# Groupe_2_final_PCB.net
KiCad netlist of a schematic drawn in EAGLE
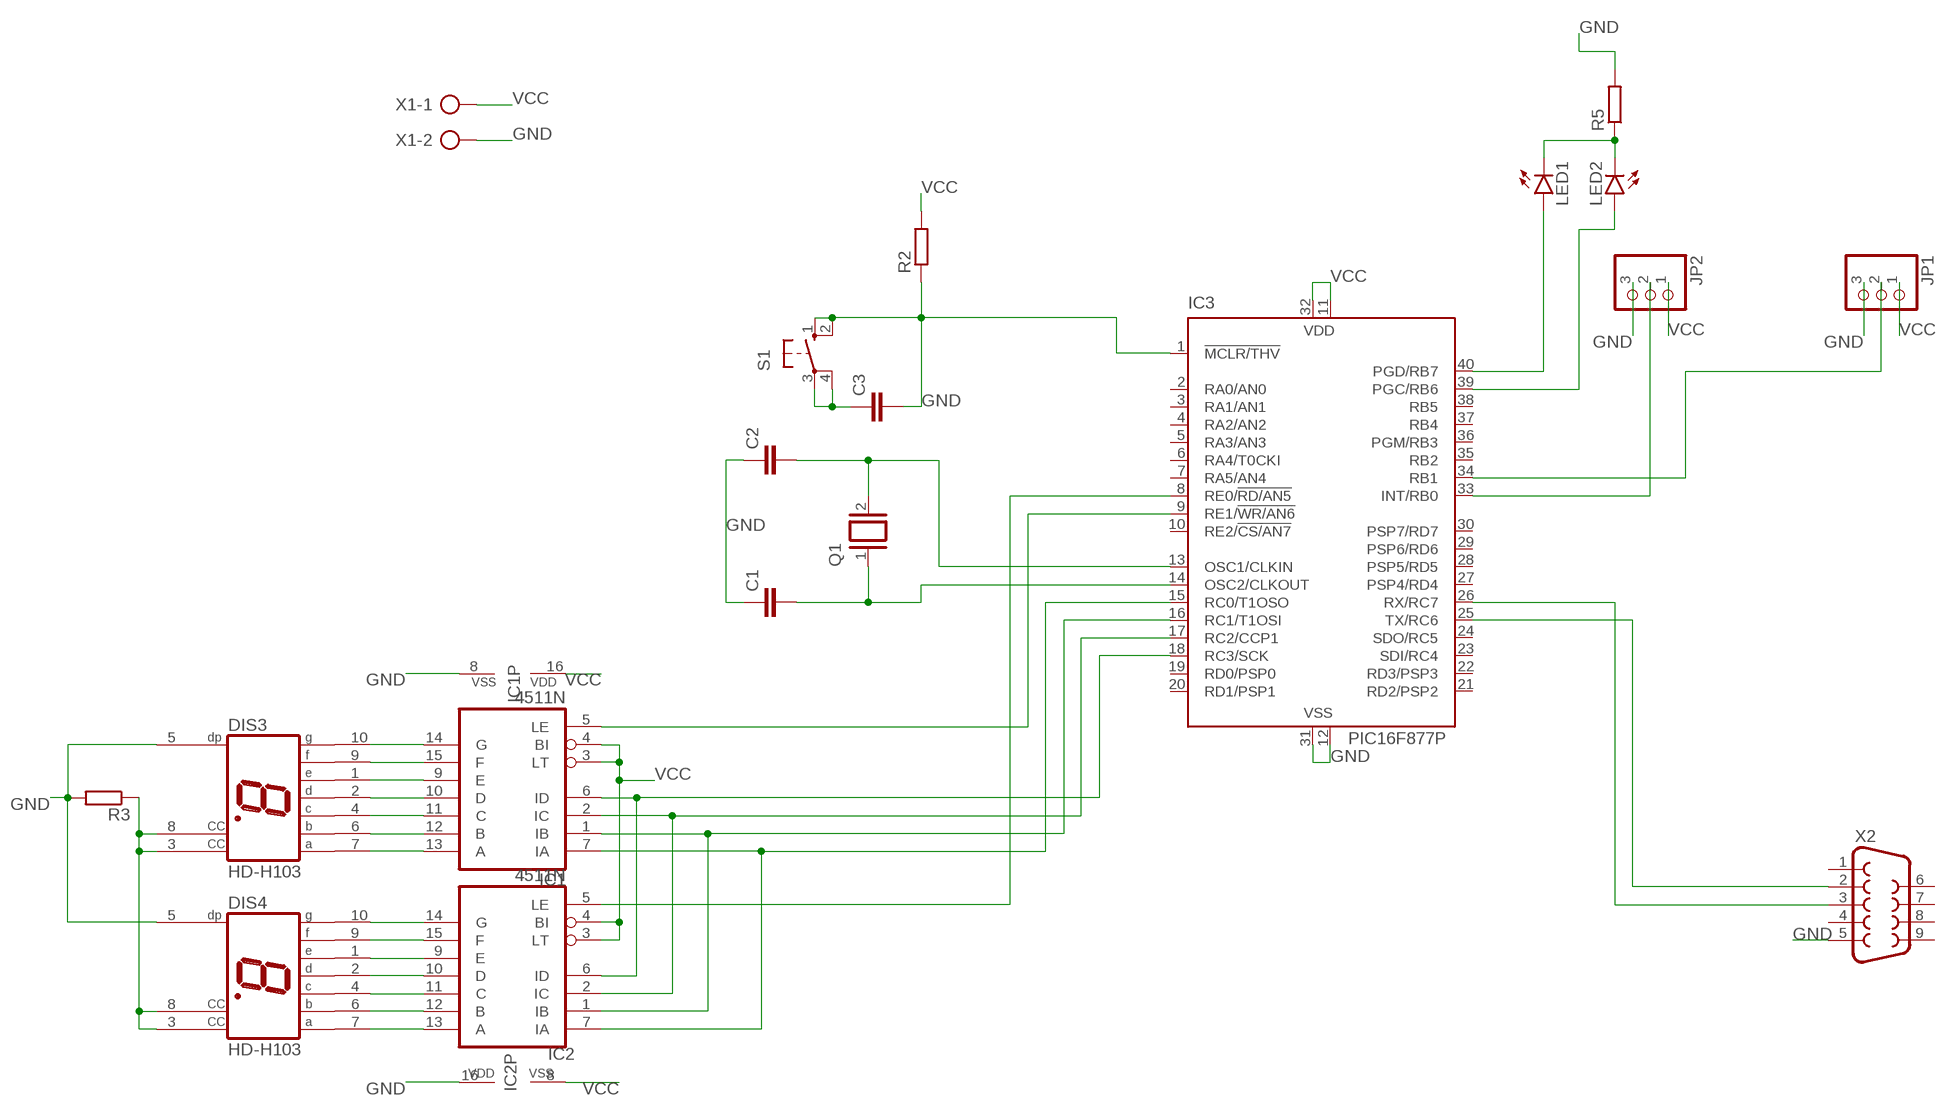
[diagram p0: schematic, sheet 1]

(export (version "E")
  (design (tool "Eeschema 10.0.6"))
  (components
    (comp (ref "C1")
      (value "C-EU025-025X050")
      (footprint "eagle-import:C025-025X050")
      (libsource (lib "eagle-import") (part "C-EU025-025X050"))
    )
    (comp (ref "C2")
      (value "C-EU025-025X050")
      (footprint "eagle-import:C025-025X050")
      (libsource (lib "eagle-import") (part "C-EU025-025X050"))
    )
    (comp (ref "C3")
      (value "C-EU025-025X050")
      (footprint "eagle-import:C025-025X050")
      (libsource (lib "eagle-import") (part "C-EU025-025X050"))
    )
    (comp (ref "DIS3")
      (value "HD-H103")
      (footprint "eagle-import:HDSP-M")
      (libsource (lib "eagle-import") (part "HD-H103"))
    )
    (comp (ref "DIS4")
      (value "HD-H103")
      (footprint "eagle-import:HDSP-M")
      (libsource (lib "eagle-import") (part "HD-H103"))
    )
    (comp (ref "IC1")
      (value "4511N")
      (footprint "eagle-import:DIL16")
      (libsource (lib "eagle-import") (part "4511N"))
    )
    (comp (ref "IC2")
      (value "4511N")
      (footprint "eagle-import:DIL16")
      (libsource (lib "eagle-import") (part "4511N"))
    )
    (comp (ref "IC3")
      (value "PIC16F877P")
      (footprint "eagle-import:DIL40")
      (fields (field (name "MF") "MICROCHIP") (field (name "MPN") "PIC16F877-04/P"))
      (libsource (lib "eagle-import") (part "PIC16F87P7"))
    )
    (comp (ref "JP1")
      (value "PINHD-1X3")
      (footprint "eagle-import:1X03")
      (libsource (lib "eagle-import") (part "PINHD-1X3"))
    )
    (comp (ref "JP2")
      (value "PINHD-1X3")
      (footprint "eagle-import:1X03")
      (libsource (lib "eagle-import") (part "PINHD-1X3"))
    )
    (comp (ref "LED1")
      (value "LED5MM")
      (footprint "eagle-import:LED5MM")
      (libsource (lib "eagle-import") (part "LED5MM"))
    )
    (comp (ref "LED2")
      (value "LED5MM")
      (footprint "eagle-import:LED5MM")
      (libsource (lib "eagle-import") (part "LED5MM"))
    )
    (comp (ref "Q1")
      (value "XTAL/S")
      (footprint "eagle-import:QS")
      (libsource (lib "eagle-import") (part "XTAL/S"))
    )
    (comp (ref "R2")
      (value "R-EU_0207/10")
      (footprint "eagle-import:0207_10")
      (libsource (lib "eagle-import") (part "R-EU_0207/10"))
    )
    (comp (ref "R3")
      (value "R-EU_0207/10")
      (footprint "eagle-import:0207_10")
      (libsource (lib "eagle-import") (part "R-EU_0207/10"))
    )
    (comp (ref "R5")
      (value "R-EU_0207/10")
      (footprint "eagle-import:0207_10")
      (libsource (lib "eagle-import") (part "R-EU_0207/10"))
    )
    (comp (ref "S1")
      (value "10-XX")
      (footprint "eagle-import:B3F-10XX")
      (fields (field (name "MPN") "B3F-1000"))
      (libsource (lib "eagle-import") (part "10-XX"))
    )
    (comp (ref "X1")
      (value "AK300/2")
      (footprint "eagle-import:AK300_2")
      (libsource (lib "eagle-import") (part "AK300/2"))
    )
    (comp (ref "X2")
      (value "F09H")
      (footprint "eagle-import:F09H")
      (libsource (lib "eagle-import") (part "F09H"))
    )
  )
  (nets
    (net (code "1") (name "/GND") (class "Default")
      (node (ref "C1") (pin "1") (pinfunction "1_1") (pintype "passive"))
      (node (ref "C2") (pin "1") (pinfunction "1_1") (pintype "passive"))
      (node (ref "C3") (pin "2") (pinfunction "2_2") (pintype "passive"))
      (node (ref "DIS3") (pin "5") (pinfunction "DP_5") (pintype "passive"))
      (node (ref "DIS4") (pin "5") (pinfunction "DP_5") (pintype "passive"))
      (node (ref "IC1") (pin "8") (pinfunction "VSS_8") (pintype "power_in"))
      (node (ref "IC2") (pin "16") (pinfunction "VDD_16") (pintype "power_in"))
      (node (ref "IC3") (pin "1") (pinfunction "~{MCLR/THV}_1") (pintype "input"))
      (node (ref "IC3") (pin "12") (pinfunction "VSS_12") (pintype "power_in"))
      (node (ref "IC3") (pin "31") (pinfunction "VSS_31") (pintype "power_in"))
      (node (ref "JP1") (pin "3") (pinfunction "3_3") (pintype "passive"))
      (node (ref "JP2") (pin "3") (pinfunction "3_3") (pintype "passive"))
      (node (ref "R2") (pin "1") (pinfunction "1_1") (pintype "passive"))
      (node (ref "R3") (pin "2") (pinfunction "2_2") (pintype "passive"))
      (node (ref "R5") (pin "2") (pinfunction "2_2") (pintype "passive"))
      (node (ref "S1") (pin "1") (pinfunction "S_1") (pintype "passive"))
      (node (ref "S1") (pin "2") (pinfunction "S1_2") (pintype "passive"))
      (node (ref "X1") (pin "2") (pinfunction "KL_2") (pintype "passive"))
      (node (ref "X2") (pin "5") (pinfunction "5_5") (pintype "passive"))
    )
    (net (code "2") (name "/VCC") (class "Default")
      (node (ref "IC1") (pin "16") (pinfunction "VDD_16") (pintype "power_in"))
      (node (ref "IC1") (pin "3") (pinfunction "LT_3") (pintype "input"))
      (node (ref "IC1") (pin "4") (pinfunction "BI_4") (pintype "input"))
      (node (ref "IC2") (pin "3") (pinfunction "LT_3") (pintype "input"))
      (node (ref "IC2") (pin "4") (pinfunction "BI_4") (pintype "input"))
      (node (ref "IC2") (pin "8") (pinfunction "VSS_8") (pintype "power_in"))
      (node (ref "IC3") (pin "11") (pinfunction "VDD_11") (pintype "power_in"))
      (node (ref "IC3") (pin "32") (pinfunction "VDD_32") (pintype "power_in"))
      (node (ref "JP1") (pin "1") (pinfunction "1_1") (pintype "passive"))
      (node (ref "JP2") (pin "1") (pinfunction "1_1") (pintype "passive"))
      (node (ref "R2") (pin "2") (pinfunction "2_2") (pintype "passive"))
      (node (ref "X1") (pin "1") (pinfunction "KL_1") (pintype "passive"))
    )
    (net (code "3") (name "Net-(DIS3-A)") (class "Default")
      (node (ref "DIS3") (pin "7") (pinfunction "A_7") (pintype "passive"))
      (node (ref "IC1") (pin "13") (pinfunction "A_13") (pintype "output"))
    )
    (net (code "4") (name "Net-(DIS3-B)") (class "Default")
      (node (ref "DIS3") (pin "6") (pinfunction "B_6") (pintype "passive"))
      (node (ref "IC1") (pin "12") (pinfunction "B_12") (pintype "output"))
    )
    (net (code "5") (name "Net-(DIS3-C)") (class "Default")
      (node (ref "DIS3") (pin "4") (pinfunction "C_4") (pintype "passive"))
      (node (ref "IC1") (pin "11") (pinfunction "C_11") (pintype "output"))
    )
    (net (code "6") (name "Net-(DIS3-CC-Pad3)") (class "Default")
      (node (ref "DIS3") (pin "3") (pinfunction "CC_3") (pintype "passive"))
      (node (ref "DIS3") (pin "8") (pinfunction "CC_8") (pintype "passive"))
      (node (ref "DIS4") (pin "3") (pinfunction "CC_3") (pintype "passive"))
      (node (ref "DIS4") (pin "8") (pinfunction "CC_8") (pintype "passive"))
      (node (ref "R3") (pin "1") (pinfunction "1_1") (pintype "passive"))
    )
    (net (code "7") (name "Net-(DIS3-D)") (class "Default")
      (node (ref "DIS3") (pin "2") (pinfunction "D_2") (pintype "passive"))
      (node (ref "IC1") (pin "10") (pinfunction "D_10") (pintype "output"))
    )
    (net (code "8") (name "Net-(DIS3-E)") (class "Default")
      (node (ref "DIS3") (pin "1") (pinfunction "E_1") (pintype "passive"))
      (node (ref "IC1") (pin "9") (pinfunction "E_9") (pintype "output"))
    )
    (net (code "9") (name "Net-(DIS3-F)") (class "Default")
      (node (ref "DIS3") (pin "9") (pinfunction "F_9") (pintype "passive"))
      (node (ref "IC1") (pin "15") (pinfunction "F_15") (pintype "output"))
    )
    (net (code "10") (name "Net-(DIS3-G)") (class "Default")
      (node (ref "DIS3") (pin "10") (pinfunction "G_10") (pintype "passive"))
      (node (ref "IC1") (pin "14") (pinfunction "G_14") (pintype "output"))
    )
    (net (code "11") (name "Net-(DIS4-A)") (class "Default")
      (node (ref "DIS4") (pin "7") (pinfunction "A_7") (pintype "passive"))
      (node (ref "IC2") (pin "13") (pinfunction "A_13") (pintype "output"))
    )
    (net (code "12") (name "Net-(DIS4-B)") (class "Default")
      (node (ref "DIS4") (pin "6") (pinfunction "B_6") (pintype "passive"))
      (node (ref "IC2") (pin "12") (pinfunction "B_12") (pintype "output"))
    )
    (net (code "13") (name "Net-(DIS4-C)") (class "Default")
      (node (ref "DIS4") (pin "4") (pinfunction "C_4") (pintype "passive"))
      (node (ref "IC2") (pin "11") (pinfunction "C_11") (pintype "output"))
    )
    (net (code "14") (name "Net-(DIS4-D)") (class "Default")
      (node (ref "DIS4") (pin "2") (pinfunction "D_2") (pintype "passive"))
      (node (ref "IC2") (pin "10") (pinfunction "D_10") (pintype "output"))
    )
    (net (code "15") (name "Net-(DIS4-E)") (class "Default")
      (node (ref "DIS4") (pin "1") (pinfunction "E_1") (pintype "passive"))
      (node (ref "IC2") (pin "9") (pinfunction "E_9") (pintype "output"))
    )
    (net (code "16") (name "Net-(DIS4-F)") (class "Default")
      (node (ref "DIS4") (pin "9") (pinfunction "F_9") (pintype "passive"))
      (node (ref "IC2") (pin "15") (pinfunction "F_15") (pintype "output"))
    )
    (net (code "17") (name "Net-(DIS4-G)") (class "Default")
      (node (ref "DIS4") (pin "10") (pinfunction "G_10") (pintype "passive"))
      (node (ref "IC2") (pin "14") (pinfunction "G_14") (pintype "output"))
    )
    (net (code "18") (name "Net-(IC1A-IA)") (class "Default")
      (node (ref "IC1") (pin "7") (pinfunction "IA_7") (pintype "input"))
      (node (ref "IC2") (pin "7") (pinfunction "IA_7") (pintype "input"))
      (node (ref "IC3") (pin "15") (pinfunction "RC0/T1OSO_15") (pintype "bidirectional"))
    )
    (net (code "19") (name "Net-(IC1A-IB)") (class "Default")
      (node (ref "IC1") (pin "1") (pinfunction "IB_1") (pintype "input"))
      (node (ref "IC2") (pin "1") (pinfunction "IB_1") (pintype "input"))
      (node (ref "IC3") (pin "16") (pinfunction "RC1/T1OSI_16") (pintype "bidirectional"))
    )
    (net (code "20") (name "Net-(IC1A-IC)") (class "Default")
      (node (ref "IC1") (pin "2") (pinfunction "IC_2") (pintype "input"))
      (node (ref "IC2") (pin "2") (pinfunction "IC_2") (pintype "input"))
      (node (ref "IC3") (pin "17") (pinfunction "RC2/CCP1_17") (pintype "bidirectional"))
    )
    (net (code "21") (name "Net-(IC1A-ID)") (class "Default")
      (node (ref "IC1") (pin "6") (pinfunction "ID_6") (pintype "input"))
      (node (ref "IC2") (pin "6") (pinfunction "ID_6") (pintype "input"))
      (node (ref "IC3") (pin "18") (pinfunction "RC3/SCK_18") (pintype "bidirectional"))
    )
    (net (code "22") (name "Net-(IC1A-LE)") (class "Default")
      (node (ref "IC1") (pin "5") (pinfunction "LE_5") (pintype "input"))
      (node (ref "IC3") (pin "9") (pinfunction "RE1/~{WR/AN6}_9") (pintype "bidirectional"))
    )
    (net (code "23") (name "Net-(IC2A-LE)") (class "Default")
      (node (ref "IC2") (pin "5") (pinfunction "LE_5") (pintype "input"))
      (node (ref "IC3") (pin "8") (pinfunction "RE0/~{RD/AN5}_8") (pintype "bidirectional"))
    )
    (net (code "24") (name "Net-(IC3-INT{slash}RB0)") (class "Default")
      (node (ref "IC3") (pin "33") (pinfunction "INT/RB0_33") (pintype "bidirectional"))
      (node (ref "JP2") (pin "2") (pinfunction "2_2") (pintype "passive"))
    )
    (net (code "25") (name "Net-(IC3-OSC1{slash}CLKIN)") (class "Default")
      (node (ref "C2") (pin "2") (pinfunction "2_2") (pintype "passive"))
      (node (ref "IC3") (pin "13") (pinfunction "OSC1/CLKIN_13") (pintype "input"))
      (node (ref "Q1") (pin "2") (pinfunction "2_2") (pintype "passive"))
    )
    (net (code "26") (name "Net-(IC3-OSC2{slash}CLKOUT)") (class "Default")
      (node (ref "C1") (pin "2") (pinfunction "2_2") (pintype "passive"))
      (node (ref "IC3") (pin "14") (pinfunction "OSC2/CLKOUT_14") (pintype "output"))
      (node (ref "Q1") (pin "1") (pinfunction "1_1") (pintype "passive"))
    )
    (net (code "27") (name "Net-(IC3-PGC{slash}RB6)") (class "Default")
      (node (ref "IC3") (pin "39") (pinfunction "PGC/RB6_39") (pintype "bidirectional"))
      (node (ref "LED2") (pin "A") (pinfunction "A_A") (pintype "passive"))
    )
    (net (code "28") (name "Net-(IC3-PGD{slash}RB7)") (class "Default")
      (node (ref "IC3") (pin "40") (pinfunction "PGD/RB7_40") (pintype "bidirectional"))
      (node (ref "LED1") (pin "A") (pinfunction "A_A") (pintype "passive"))
    )
    (net (code "29") (name "Net-(IC3-RB1)") (class "Default")
      (node (ref "IC3") (pin "34") (pinfunction "RB1_34") (pintype "bidirectional"))
      (node (ref "JP1") (pin "2") (pinfunction "2_2") (pintype "passive"))
    )
    (net (code "30") (name "Net-(IC3-RX{slash}RC7)") (class "Default")
      (node (ref "IC3") (pin "26") (pinfunction "RX/RC7_26") (pintype "bidirectional"))
      (node (ref "X2") (pin "3") (pinfunction "3_3") (pintype "passive"))
    )
    (net (code "31") (name "Net-(IC3-TX{slash}RC6)") (class "Default")
      (node (ref "IC3") (pin "25") (pinfunction "TX/RC6_25") (pintype "bidirectional"))
      (node (ref "X2") (pin "2") (pinfunction "2_2") (pintype "passive"))
    )
    (net (code "32") (name "Net-(LED1-C)") (class "Default")
      (node (ref "LED1") (pin "K") (pinfunction "C_K") (pintype "passive"))
      (node (ref "LED2") (pin "K") (pinfunction "C_K") (pintype "passive"))
      (node (ref "R5") (pin "1") (pinfunction "1_1") (pintype "passive"))
    )
    (net (code "33") (name "Net-(S1-P)") (class "Default")
      (node (ref "C3") (pin "1") (pinfunction "1_1") (pintype "passive"))
      (node (ref "S1") (pin "3") (pinfunction "P_3") (pintype "passive"))
      (node (ref "S1") (pin "4") (pinfunction "P1_4") (pintype "passive"))
    )
    (net (code "34") (name "unconnected-(IC3-PGM{slash}RB3-Pad36)") (class "Default")
      (node (ref "IC3") (pin "36") (pinfunction "PGM/RB3_36") (pintype "bidirectional"))
    )
    (net (code "35") (name "unconnected-(IC3-PSP4{slash}RD4-Pad27)") (class "Default")
      (node (ref "IC3") (pin "27") (pinfunction "PSP4/RD4_27") (pintype "bidirectional"))
    )
    (net (code "36") (name "unconnected-(IC3-PSP5{slash}RD5-Pad28)") (class "Default")
      (node (ref "IC3") (pin "28") (pinfunction "PSP5/RD5_28") (pintype "bidirectional"))
    )
    (net (code "37") (name "unconnected-(IC3-PSP6{slash}RD6-Pad29)") (class "Default")
      (node (ref "IC3") (pin "29") (pinfunction "PSP6/RD6_29") (pintype "bidirectional"))
    )
    (net (code "38") (name "unconnected-(IC3-PSP7{slash}RD7-Pad30)") (class "Default")
      (node (ref "IC3") (pin "30") (pinfunction "PSP7/RD7_30") (pintype "bidirectional"))
    )
    (net (code "39") (name "unconnected-(IC3-RA0{slash}AN0-Pad2)") (class "Default")
      (node (ref "IC3") (pin "2") (pinfunction "RA0/AN0_2") (pintype "bidirectional"))
    )
    (net (code "40") (name "unconnected-(IC3-RA1{slash}AN1-Pad3)") (class "Default")
      (node (ref "IC3") (pin "3") (pinfunction "RA1/AN1_3") (pintype "bidirectional"))
    )
    (net (code "41") (name "unconnected-(IC3-RA2{slash}AN2-Pad4)") (class "Default")
      (node (ref "IC3") (pin "4") (pinfunction "RA2/AN2_4") (pintype "bidirectional"))
    )
    (net (code "42") (name "unconnected-(IC3-RA3{slash}AN3-Pad5)") (class "Default")
      (node (ref "IC3") (pin "5") (pinfunction "RA3/AN3_5") (pintype "bidirectional"))
    )
    (net (code "43") (name "unconnected-(IC3-RA4{slash}T0CKI-Pad6)") (class "Default")
      (node (ref "IC3") (pin "6") (pinfunction "RA4/T0CKI_6") (pintype "bidirectional"))
    )
    (net (code "44") (name "unconnected-(IC3-RA5{slash}AN4-Pad7)") (class "Default")
      (node (ref "IC3") (pin "7") (pinfunction "RA5/AN4_7") (pintype "bidirectional"))
    )
    (net (code "45") (name "unconnected-(IC3-RB2-Pad35)") (class "Default")
      (node (ref "IC3") (pin "35") (pinfunction "RB2_35") (pintype "bidirectional"))
    )
    (net (code "46") (name "unconnected-(IC3-RB4-Pad37)") (class "Default")
      (node (ref "IC3") (pin "37") (pinfunction "RB4_37") (pintype "bidirectional"))
    )
    (net (code "47") (name "unconnected-(IC3-RB5-Pad38)") (class "Default")
      (node (ref "IC3") (pin "38") (pinfunction "RB5_38") (pintype "bidirectional"))
    )
    (net (code "48") (name "unconnected-(IC3-RD0{slash}PSP0-Pad19)") (class "Default")
      (node (ref "IC3") (pin "19") (pinfunction "RD0/PSP0_19") (pintype "bidirectional"))
    )
    (net (code "49") (name "unconnected-(IC3-RD1{slash}PSP1-Pad20)") (class "Default")
      (node (ref "IC3") (pin "20") (pinfunction "RD1/PSP1_20") (pintype "bidirectional"))
    )
    (net (code "50") (name "unconnected-(IC3-RD2{slash}PSP2-Pad21)") (class "Default")
      (node (ref "IC3") (pin "21") (pinfunction "RD2/PSP2_21") (pintype "bidirectional"))
    )
    (net (code "51") (name "unconnected-(IC3-RD3{slash}PSP3-Pad22)") (class "Default")
      (node (ref "IC3") (pin "22") (pinfunction "RD3/PSP3_22") (pintype "bidirectional"))
    )
    (net (code "52") (name "unconnected-(IC3-RE2{slash}~{CS{slash}AN7}-Pad10)") (class "Default")
      (node (ref "IC3") (pin "10") (pinfunction "RE2/~{CS/AN7}_10") (pintype "bidirectional"))
    )
    (net (code "53") (name "unconnected-(IC3-SDI{slash}RC4-Pad23)") (class "Default")
      (node (ref "IC3") (pin "23") (pinfunction "SDI/RC4_23") (pintype "bidirectional"))
    )
    (net (code "54") (name "unconnected-(IC3-SDO{slash}RC5-Pad24)") (class "Default")
      (node (ref "IC3") (pin "24") (pinfunction "SDO/RC5_24") (pintype "bidirectional"))
    )
    (net (code "55") (name "unconnected-(X2-Pad1)") (class "Default")
      (node (ref "X2") (pin "1") (pinfunction "1_1") (pintype "passive"))
    )
    (net (code "56") (name "unconnected-(X2-Pad4)") (class "Default")
      (node (ref "X2") (pin "4") (pinfunction "4_4") (pintype "passive"))
    )
    (net (code "57") (name "unconnected-(X2-Pad6)") (class "Default")
      (node (ref "X2") (pin "6") (pinfunction "6_6") (pintype "passive"))
    )
    (net (code "58") (name "unconnected-(X2-Pad7)") (class "Default")
      (node (ref "X2") (pin "7") (pinfunction "7_7") (pintype "passive"))
    )
    (net (code "59") (name "unconnected-(X2-Pad8)") (class "Default")
      (node (ref "X2") (pin "8") (pinfunction "8_8") (pintype "passive"))
    )
    (net (code "60") (name "unconnected-(X2-Pad9)") (class "Default")
      (node (ref "X2") (pin "9") (pinfunction "9_9") (pintype "passive"))
    )
  )
)
